# CAN.net
KiCad netlist of a schematic drawn in Altium Designer
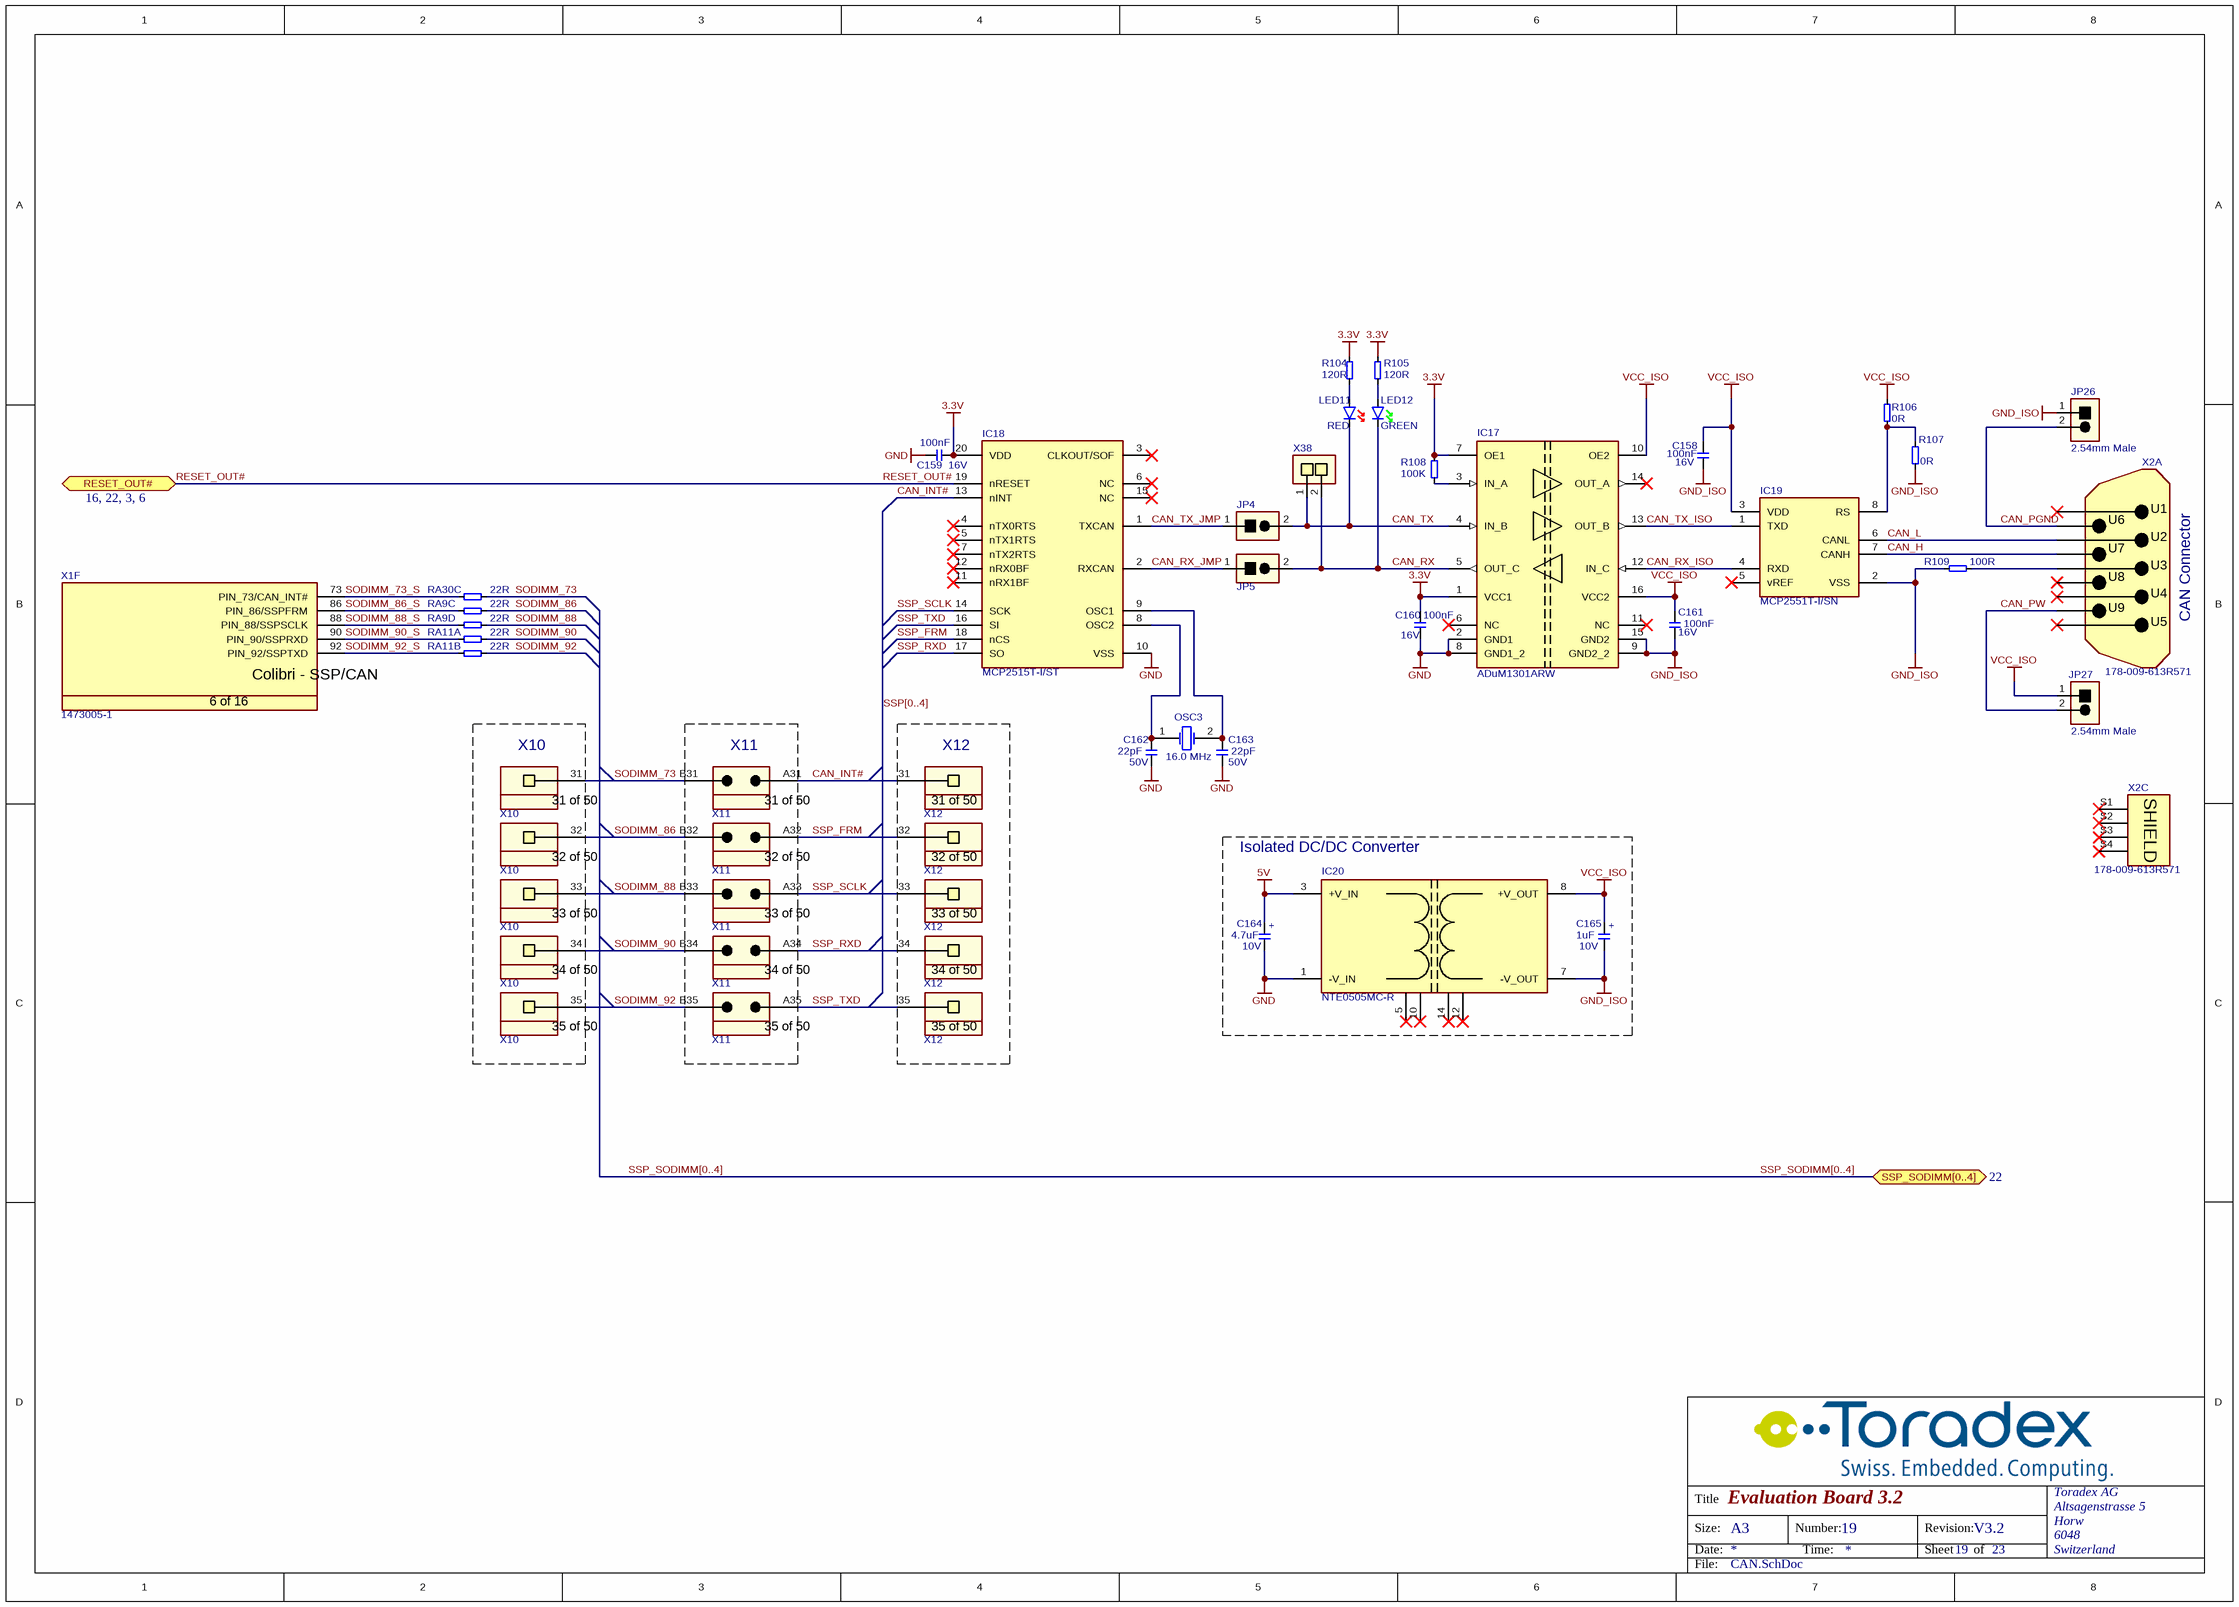
[diagram p0: CAN.SchDoc]

(export (version "E")
  (design (tool "Eeschema 10.0.6"))
  (components
    (comp (ref "C158")
      (value "100nF")
      (footprint "T_CAPC0603X33N")
      (description "Capacitor Ceramic X7R 100nF 16V 10% 0603")
      (fields (field (name "TOLERANCE") "10%") (field (name "RATING") "16V"))
      (libsource (lib "Evaluation Board") (part "C-X7R-100nF-16V-10%-0603"))
    )
    (comp (ref "C159")
      (value "100nF")
      (footprint "T_CAPC0603X33N")
      (description "Capacitor Ceramic X7R 100nF 16V 10% 0603")
      (fields (field (name "TOLERANCE") "10%") (field (name "RATING") "16V"))
      (libsource (lib "Evaluation Board") (part "C-X7R-100nF-16V-10%-0603"))
    )
    (comp (ref "C160")
      (value "100nF")
      (footprint "T_CAPC0603X33N")
      (description "Capacitor Ceramic X7R 100nF 16V 10% 0603")
      (fields (field (name "TOLERANCE") "10%") (field (name "RATING") "16V"))
      (libsource (lib "Evaluation Board") (part "C-X7R-100nF-16V-10%-0603"))
    )
    (comp (ref "C161")
      (value "100nF")
      (footprint "T_CAPC0603X33N")
      (description "Capacitor Ceramic X7R 100nF 16V 10% 0603")
      (fields (field (name "TOLERANCE") "10%") (field (name "RATING") "16V"))
      (libsource (lib "Evaluation Board") (part "C-X7R-100nF-16V-10%-0603"))
    )
    (comp (ref "C162")
      (value "22pF")
      (footprint "T_CAPC0603X33N")
      (description "Capacitor Ceramic NPO 22pF 50V 5% 0603")
      (fields (field (name "TOLERANCE") "5%") (field (name "RATING") "50V"))
      (libsource (lib "Evaluation Board") (part "C-NPO-22pF-50V-5%-0603"))
    )
    (comp (ref "C163")
      (value "22pF")
      (footprint "T_CAPC0603X33N")
      (description "Capacitor Ceramic NPO 22pF 50V 5% 0603")
      (fields (field (name "TOLERANCE") "5%") (field (name "RATING") "50V"))
      (libsource (lib "Evaluation Board") (part "C-NPO-22pF-50V-5%-0603"))
    )
    (comp (ref "C164")
      (value "4.7uF")
      (footprint "T_CAPMP3216X180N")
      (description "Capacitor TA 4.7uF 10V 20% 3216")
      (fields (field (name "TOLERANCE") "20%") (field (name "RATING") "10V"))
      (libsource (lib "Evaluation Board") (part "C-TA-4.7uF-10V-20%-3216"))
    )
    (comp (ref "C165")
      (value "1uF")
      (footprint "T_CAPMP3216X180N")
      (description "Capacitor TA 1uF 10V 20% 3216")
      (fields (field (name "TOLERANCE") "20%") (field (name "RATING") "10V"))
      (libsource (lib "Evaluation Board") (part "C-TA-1uF-10V-20%-3216"))
    )
    (comp (ref "IC17")
      (value "ADuM1301ARW")
      (footprint "T_AD_ADuM1300ARW")
      (description "Digital Isolator")
      (fields (field (name "MANUFACTURER PART NO.") "ADuM1301ARW"))
      (libsource (lib "Evaluation Board") (part "IC-AD-ADuM1301ARW"))
    )
    (comp (ref "IC18")
      (value "MCP2515")
      (footprint "T_MC_MCP2515T-I/ST")
      (description "CAN controller with SPI Interface")
      (fields (field (name "MANUFACTURER PART NO.") "MCP2515T-I/ST"))
      (libsource (lib "Evaluation Board") (part "IC-MC-MCP2515T-I/ST"))
    )
    (comp (ref "IC19")
      (value "MCP2551T-I/SN")
      (footprint "SOIC127P600X173-8N")
      (description "High speed CAN Transceiver")
      (fields (field (name "MANUFACTURER PART NO.") "MCP2551T-I/SN"))
      (libsource (lib "Evaluation Board") (part "IC-MC-MCP2551T-I/SN"))
    )
    (comp (ref "IC20")
      (value "NTE0505MC-R")
      (footprint "T_MURATA_NTE0505MC-R")
      (description "Isolated DC/DC Converter")
      (fields (field (name "MANUFACTURER PART NO.") "NTE0505MC-R"))
      (libsource (lib "Evaluation Board") (part "IC-MUR-NTE0505MC-R"))
    )
    (comp (ref "JP4")
      (value "TSW-101-07-G-D")
      (footprint "T_Samtec_TSW-101-07-G-D")
      (description "Header male, 1x2 Pins, 2.54 mm pitch")
      (libsource (lib "Evaluation Board") (part "CON-Samtec-TSW-101-07-G-D_1"))
    )
    (comp (ref "JP5")
      (value "TSW-101-07-G-D")
      (footprint "T_Samtec_TSW-101-07-G-D")
      (description "Header male, 1x2 Pins, 2.54 mm pitch")
      (libsource (lib "Evaluation Board") (part "CON-Samtec-TSW-101-07-G-D_1"))
    )
    (comp (ref "JP26")
      (value "TSW-101-07-G-D")
      (footprint "T_Samtec_TSW-101-07-G-D")
      (description "Header male, 1x2 Pins, 2.54 mm pitch")
      (libsource (lib "Evaluation Board") (part "CON-Samtec-TSW-101-07-G-D"))
    )
    (comp (ref "JP27")
      (value "TSW-101-07-G-D")
      (footprint "T_Samtec_TSW-101-07-G-D")
      (description "Header male, 1x2 Pins, 2.54 mm pitch")
      (libsource (lib "Evaluation Board") (part "CON-Samtec-TSW-101-07-G-D"))
    )
    (comp (ref "LED11")
      (value "LS T670-K1L2-1")
      (footprint "T_Osram_T670_RED")
      (description "LED red, Osram LS T670-K1L2-1")
      (fields (field (name "COLOR") "RED"))
      (libsource (lib "Evaluation Board") (part "LED-Osram-LS T670-K1L2-1"))
    )
    (comp (ref "LED12")
      (value "LG T670-K1L2-1")
      (footprint "T_Osram_T670_GREEN")
      (description "LED green Osram LG T670-K1L2-1")
      (fields (field (name "COLOR") "GREEN"))
      (libsource (lib "Evaluation Board") (part "LED-Osram-T670-K1L2-1"))
    )
    (comp (ref "OSC3")
      (value "16.0 MHz")
      (footprint "T_RAKON_12SMX")
      (description "Quartz 16.0 MHz")
      (fields
        (field (name "TOLERANCE") "30ppm")
        (field (name "MANUFACTURER PART NO.") "12SMX (B) 30/5020/16")
      )
      (libsource (lib "Evaluation Board") (part "OSC-RAKON-12SMX (B) 30/5020/16-16.0 MHz-30ppm-7.5x5.2mm"))
    )
    (comp (ref "R104")
      (value "120R")
      (footprint "T_RESC0603X30N")
      (description "Resistor 120 ohm 63mW 5% 0603")
      (fields (field (name "TOLERANCE") "5%"))
      (libsource (lib "Evaluation Board") (part "R-120R-63mW-5%-0603"))
    )
    (comp (ref "R105")
      (value "120R")
      (footprint "T_RESC0603X30N")
      (description "Resistor 120 ohm 63mW 5% 0603")
      (fields (field (name "TOLERANCE") "5%"))
      (libsource (lib "Evaluation Board") (part "R-120R-63mW-5%-0603"))
    )
    (comp (ref "R106")
      (value "0R")
      (footprint "T_RESC0603X30N")
      (description "Resistor 0 ohm 63mW 1% 0603")
      (fields (field (name "TOLERANCE") "1%"))
      (libsource (lib "Evaluation Board") (part "R-0R-63mW-1%-0603"))
    )
    (comp (ref "R107")
      (value "0R")
      (footprint "T_RESC0603X30N")
      (description "Resistor 0 ohm 63mW 1% 0603")
      (fields (field (name "TOLERANCE") "1%"))
      (libsource (lib "Evaluation Board") (part "R-0R-63mW-1%-0603"))
    )
    (comp (ref "R108")
      (value "100K")
      (footprint "T_RESC0603X30N")
      (description "Resistor 100 Kohm 63mW 5% 0603")
      (fields (field (name "TOLERANCE") "5%"))
      (libsource (lib "Evaluation Board") (part "R-100KR-63mW-5%-0603"))
    )
    (comp (ref "R109")
      (value "100R")
      (footprint "T_RESC0603X30N")
      (description "Resistor 100 ohm 63mW 5% 0603")
      (fields (field (name "TOLERANCE") "5%"))
      (libsource (lib "Evaluation Board") (part "R-100R-63mW-5%-0603"))
    )
    (comp (ref "RA9")
      (value "22R")
      (footprint "T_Resistor_Array_X4")
      (description "Resistor Array 22 R 63mW 5% 1206")
      (fields (field (name "TOLERANCE") "5%"))
      (libsource (lib "Evaluation Board") (part "RA-22R-63mW-5%-1206-div"))
    )
    (comp (ref "RA11")
      (value "22R")
      (footprint "T_Resistor_Array_X4")
      (description "Resistor Array 22 R 63mW 5% 1206")
      (fields (field (name "TOLERANCE") "5%"))
      (libsource (lib "Evaluation Board") (part "RA-22R-63mW-5%-1206-div"))
    )
    (comp (ref "RA30")
      (value "22R")
      (footprint "T_Resistor_Array_X4")
      (description "Resistor Array 22 R 63mW 5% 1206")
      (fields (field (name "TOLERANCE") "5%"))
      (libsource (lib "Evaluation Board") (part "RA-22R-63mW-5%-1206-div"))
    )
    (comp (ref "X1")
      (value "CON-Tyco-1473005-1-200-0.6mm")
      (footprint "T_Tyco_1473005-1")
      (description "SODIMM Connector")
      (fields (field (name "MANUFACTURER PART NO.") "1473005-1"))
      (libsource (lib "Evaluation Board") (part "CON-Tyco-1473005-1-200-0.6mm"))
    )
    (comp (ref "X2")
      (value "178-009-613R571")
      (footprint "T_NorComp_178-YYY-613R691")
      (description "RS232 Connector 9 pins male")
      (fields (field (name "MANUFACTURER PART NO.") "178-009-613R571"))
      (libsource (lib "Evaluation Board") (part "CON-NorComp-178-009-613R571"))
    )
    (comp (ref "X10")
      (value "SSW-110-01-G-S")
      (footprint "T_Samtec_SSW-110-01-G-S")
      (description "Header 1x50 pin 2.54mm pitch")
      (libsource (lib "") (part "CON-Samtec-SSW-110-01-G-S_1"))
    )
    (comp (ref "X11")
      (value "TSW-110-07-G-D")
      (footprint "T_Samtec_TSW-110-07-G-D")
      (description "Header 2x50 pin 2.54mm pitch")
      (libsource (lib "Evaluation Board") (part "CON-Samtec-TSW-110-07-G-D"))
    )
    (comp (ref "X12")
      (value "SSW-110-01-G-S")
      (footprint "T_Samtec_SSW-110-01-G-S")
      (description "Header 1x50 pin 2.54mm pitch")
      (libsource (lib "Evaluation Board") (part "CON-Samtec-SSW-110-01-G-S"))
    )
    (comp (ref "X38")
      (value "SSW-102-01-G-S")
      (footprint "T_Samtec_SSW-102-01-G-S")
      (description "Receptacle Female, 1x2 Pins, 2.54 mm pitch")
      (libsource (lib "Evaluation Board") (part "CON-Samtec-SSW-102-01-G-S"))
    )
  )
  (nets
    (net (code "11") (name "/CAN_H") (class "Default")
      (node (ref "IC19") (pin "7") (pinfunction "CANH_7") (pintype "passive"))
      (node (ref "X2") (pin "U7") (pinfunction "RTS_U7") (pintype "passive"))
    )
    (net (code "12") (name "/CAN_INT#") (class "Default")
      (node (ref "IC18") (pin "13") (pinfunction "nINT_13") (pintype "passive"))
      (node (ref "X11") (pin "A31") (pinfunction "A31_A31") (pintype "passive"))
      (node (ref "X12") (pin "31") (pinfunction "31_31") (pintype "passive"))
    )
    (net (code "13") (name "/CAN_L") (class "Default")
      (node (ref "IC19") (pin "6") (pinfunction "CANL_6") (pintype "passive"))
      (node (ref "X2") (pin "U2") (pinfunction "RXD_U2") (pintype "passive"))
    )
    (net (code "14") (name "/CAN_PGND") (class "Default")
      (node (ref "JP26") (pin "2") (pinfunction "2_2") (pintype "passive"))
      (node (ref "X2") (pin "U6") (pinfunction "DSR_U6") (pintype "passive"))
    )
    (net (code "15") (name "/CAN_PW") (class "Default")
      (node (ref "JP27") (pin "2") (pinfunction "2_2") (pintype "passive"))
      (node (ref "X2") (pin "U9") (pinfunction "RI_U9") (pintype "passive"))
    )
    (net (code "16") (name "/CAN_RX") (class "Default")
      (node (ref "IC17") (pin "5") (pinfunction "OUT_C_5") (pintype "output"))
      (node (ref "JP5") (pin "2") (pinfunction "2_2") (pintype "passive"))
      (node (ref "LED12") (pin "K") (pinfunction "K_K") (pintype "passive"))
      (node (ref "X38") (pin "2") (pinfunction "2_2") (pintype "passive"))
    )
    (net (code "17") (name "/CAN_RX_ISO") (class "Default")
      (node (ref "IC17") (pin "12") (pinfunction "IN_C_12") (pintype "input"))
      (node (ref "IC19") (pin "4") (pinfunction "RXD_4") (pintype "passive"))
    )
    (net (code "18") (name "/CAN_RX_JMP") (class "Default")
      (node (ref "IC18") (pin "2") (pinfunction "RXCAN_2") (pintype "passive"))
      (node (ref "JP5") (pin "1") (pinfunction "1_1") (pintype "passive"))
    )
    (net (code "19") (name "/CAN_TX") (class "Default")
      (node (ref "IC17") (pin "4") (pinfunction "IN_B_4") (pintype "input"))
      (node (ref "JP4") (pin "2") (pinfunction "2_2") (pintype "passive"))
      (node (ref "LED11") (pin "K") (pinfunction "K_K") (pintype "passive"))
      (node (ref "X38") (pin "1") (pinfunction "1_1") (pintype "passive"))
    )
    (net (code "20") (name "/CAN_TX_ISO") (class "Default")
      (node (ref "IC17") (pin "13") (pinfunction "OUT_B_13") (pintype "output"))
      (node (ref "IC19") (pin "1") (pinfunction "TXD_1") (pintype "passive"))
    )
    (net (code "21") (name "/CAN_TX_JMP") (class "Default")
      (node (ref "IC18") (pin "1") (pinfunction "TXCAN_1") (pintype "passive"))
      (node (ref "JP4") (pin "1") (pinfunction "1_1") (pintype "passive"))
    )
    (net (code "22") (name "/RESET_OUT#") (class "Default")
      (node (ref "IC18") (pin "19") (pinfunction "nRESET_19") (pintype "passive"))
    )
    (net (code "23") (name "/SODIMM_73") (class "Default")
      (node (ref "RA30") (pin "7") (pinfunction "7_7") (pintype "passive"))
      (node (ref "X10") (pin "31") (pinfunction "31_31") (pintype "passive"))
      (node (ref "X11") (pin "B31") (pinfunction "B31_B31") (pintype "passive"))
    )
    (net (code "24") (name "/SODIMM_73_S") (class "Default")
      (node (ref "RA30") (pin "3") (pinfunction "3_3") (pintype "passive"))
      (node (ref "X1") (pin "73") (pinfunction "PIN_73/CAN_INT#_73") (pintype "passive"))
    )
    (net (code "25") (name "/SODIMM_86") (class "Default")
      (node (ref "RA9") (pin "7") (pinfunction "7_7") (pintype "passive"))
      (node (ref "X10") (pin "32") (pinfunction "32_32") (pintype "passive"))
      (node (ref "X11") (pin "B32") (pinfunction "B32_B32") (pintype "passive"))
    )
    (net (code "26") (name "/SODIMM_86_S") (class "Default")
      (node (ref "RA9") (pin "3") (pinfunction "3_3") (pintype "passive"))
      (node (ref "X1") (pin "86") (pinfunction "PIN_86/SSPFRM_86") (pintype "passive"))
    )
    (net (code "27") (name "/SODIMM_88") (class "Default")
      (node (ref "RA9") (pin "8") (pinfunction "8_8") (pintype "passive"))
      (node (ref "X10") (pin "33") (pinfunction "33_33") (pintype "passive"))
      (node (ref "X11") (pin "B33") (pinfunction "B33_B33") (pintype "passive"))
    )
    (net (code "28") (name "/SODIMM_88_S") (class "Default")
      (node (ref "RA9") (pin "4") (pinfunction "4_4") (pintype "passive"))
      (node (ref "X1") (pin "88") (pinfunction "PIN_88/SSPSCLK_88") (pintype "passive"))
    )
    (net (code "29") (name "/SODIMM_90") (class "Default")
      (node (ref "RA11") (pin "5") (pinfunction "5_5") (pintype "passive"))
      (node (ref "X10") (pin "34") (pinfunction "34_34") (pintype "passive"))
      (node (ref "X11") (pin "B34") (pinfunction "B34_B34") (pintype "passive"))
    )
    (net (code "30") (name "/SODIMM_90_S") (class "Default")
      (node (ref "RA11") (pin "1") (pinfunction "1_1") (pintype "passive"))
      (node (ref "X1") (pin "90") (pinfunction "PIN_90/SSPRXD_90") (pintype "passive"))
    )
    (net (code "31") (name "/SODIMM_92") (class "Default")
      (node (ref "RA11") (pin "6") (pinfunction "6_6") (pintype "passive"))
      (node (ref "X10") (pin "35") (pinfunction "35_35") (pintype "passive"))
      (node (ref "X11") (pin "B35") (pinfunction "B35_B35") (pintype "passive"))
    )
    (net (code "32") (name "/SODIMM_92_S") (class "Default")
      (node (ref "RA11") (pin "2") (pinfunction "2_2") (pintype "passive"))
      (node (ref "X1") (pin "92") (pinfunction "PIN_92/SSPTXD_92") (pintype "passive"))
    )
    (net (code "34") (name "/SSP_FRM") (class "Default")
      (node (ref "IC18") (pin "18") (pinfunction "nCS_18") (pintype "passive"))
      (node (ref "X11") (pin "A32") (pinfunction "A32_A32") (pintype "passive"))
      (node (ref "X12") (pin "32") (pinfunction "32_32") (pintype "passive"))
    )
    (net (code "35") (name "/SSP_RXD") (class "Default")
      (node (ref "IC18") (pin "17") (pinfunction "SO_17") (pintype "passive"))
      (node (ref "X11") (pin "A34") (pinfunction "A34_A34") (pintype "passive"))
      (node (ref "X12") (pin "34") (pinfunction "34_34") (pintype "passive"))
    )
    (net (code "36") (name "/SSP_SCLK") (class "Default")
      (node (ref "IC18") (pin "14") (pinfunction "SCK_14") (pintype "passive"))
      (node (ref "X11") (pin "A33") (pinfunction "A33_A33") (pintype "passive"))
      (node (ref "X12") (pin "33") (pinfunction "33_33") (pintype "passive"))
    )
    (net (code "38") (name "/SSP_TXD") (class "Default")
      (node (ref "IC18") (pin "16") (pinfunction "SI_16") (pintype "passive"))
      (node (ref "X11") (pin "A35") (pinfunction "A35_A35") (pintype "passive"))
      (node (ref "X12") (pin "35") (pinfunction "35_35") (pintype "passive"))
    )
    (net (code "39") (name "3.3V") (class "Default")
      (node (ref "C159") (pin "1") (pinfunction "1_1") (pintype "passive"))
      (node (ref "C160") (pin "2") (pinfunction "2_2") (pintype "passive"))
      (node (ref "IC17") (pin "1") (pinfunction "VCC1_1") (pintype "passive"))
      (node (ref "IC17") (pin "7") (pinfunction "OE1_7") (pintype "passive"))
      (node (ref "IC18") (pin "20") (pinfunction "VDD_20") (pintype "passive"))
      (node (ref "R104") (pin "1") (pinfunction "1_1") (pintype "passive"))
      (node (ref "R105") (pin "1") (pinfunction "1_1") (pintype "passive"))
      (node (ref "R108") (pin "2") (pinfunction "2_2") (pintype "passive"))
    )
    (net (code "40") (name "5V") (class "Default")
      (node (ref "C164") (pin "1") (pinfunction "1_1") (pintype "passive"))
      (node (ref "IC20") (pin "3") (pinfunction "+V_IN_3") (pintype "power_in"))
    )
    (net (code "41") (name "GND") (class "Default")
      (node (ref "C159") (pin "2") (pinfunction "2_2") (pintype "passive"))
      (node (ref "C160") (pin "1") (pinfunction "1_1") (pintype "passive"))
      (node (ref "C162") (pin "1") (pinfunction "1_1") (pintype "passive"))
      (node (ref "C163") (pin "1") (pinfunction "1_1") (pintype "passive"))
      (node (ref "C164") (pin "2") (pinfunction "2_2") (pintype "passive"))
      (node (ref "IC17") (pin "2") (pinfunction "GND1_2") (pintype "power_in"))
      (node (ref "IC17") (pin "8") (pinfunction "GND1_2_8") (pintype "power_in"))
      (node (ref "IC18") (pin "10") (pinfunction "VSS_10") (pintype "power_in"))
      (node (ref "IC20") (pin "1") (pinfunction "-V_IN_1") (pintype "power_in"))
    )
    (net (code "42") (name "GND_ISO") (class "Default")
      (node (ref "C158") (pin "1") (pinfunction "1_1") (pintype "passive"))
      (node (ref "C161") (pin "1") (pinfunction "1_1") (pintype "passive"))
      (node (ref "C165") (pin "2") (pinfunction "2_2") (pintype "passive"))
      (node (ref "IC17") (pin "15") (pinfunction "GND2_15") (pintype "power_in"))
      (node (ref "IC17") (pin "9") (pinfunction "GND2_2_9") (pintype "power_in"))
      (node (ref "IC19") (pin "2") (pinfunction "VSS_2") (pintype "passive"))
      (node (ref "IC20") (pin "7") (pinfunction "-V_OUT_7") (pintype "power_in"))
      (node (ref "JP26") (pin "1") (pinfunction "1_1") (pintype "passive"))
      (node (ref "R107") (pin "1") (pinfunction "1_1") (pintype "passive"))
      (node (ref "R109") (pin "2") (pinfunction "2_2") (pintype "passive"))
    )
    (net (code "43") (name "Net-(IC17-IN_A)") (class "Default")
      (node (ref "IC17") (pin "3") (pinfunction "IN_A_3") (pintype "input"))
      (node (ref "R108") (pin "1") (pinfunction "1_1") (pintype "passive"))
    )
    (net (code "44") (name "Net-(IC18-OSC1)") (class "Default")
      (node (ref "C163") (pin "2") (pinfunction "2_2") (pintype "passive"))
      (node (ref "IC18") (pin "9") (pinfunction "OSC1_9") (pintype "passive"))
      (node (ref "OSC3") (pin "2") (pinfunction "OSC2_2") (pintype "passive"))
    )
    (net (code "45") (name "Net-(IC18-OSC2)") (class "Default")
      (node (ref "C162") (pin "2") (pinfunction "2_2") (pintype "passive"))
      (node (ref "IC18") (pin "8") (pinfunction "OSC2_8") (pintype "passive"))
      (node (ref "OSC3") (pin "1") (pinfunction "OSC1_1") (pintype "passive"))
    )
    (net (code "46") (name "Net-(IC19-RS)") (class "Default")
      (node (ref "IC19") (pin "8") (pinfunction "RS_8") (pintype "passive"))
      (node (ref "R106") (pin "1") (pinfunction "1_1") (pintype "passive"))
      (node (ref "R107") (pin "2") (pinfunction "2_2") (pintype "passive"))
    )
    (net (code "47") (name "Net-(LED11-PadA)") (class "Default")
      (node (ref "LED11") (pin "A") (pinfunction "A_A") (pintype "passive"))
      (node (ref "R104") (pin "2") (pinfunction "2_2") (pintype "passive"))
    )
    (net (code "48") (name "Net-(LED12-PadA)") (class "Default")
      (node (ref "LED12") (pin "A") (pinfunction "A_A") (pintype "passive"))
      (node (ref "R105") (pin "2") (pinfunction "2_2") (pintype "passive"))
    )
    (net (code "49") (name "Net-(X2A-TXD)") (class "Default")
      (node (ref "R109") (pin "1") (pinfunction "1_1") (pintype "passive"))
      (node (ref "X2") (pin "U3") (pinfunction "TXD_U3") (pintype "passive"))
    )
    (net (code "50") (name "VCC_ISO") (class "Default")
      (node (ref "C158") (pin "2") (pinfunction "2_2") (pintype "passive"))
      (node (ref "C161") (pin "2") (pinfunction "2_2") (pintype "passive"))
      (node (ref "C165") (pin "1") (pinfunction "1_1") (pintype "passive"))
      (node (ref "IC17") (pin "10") (pinfunction "OE2_10") (pintype "passive"))
      (node (ref "IC17") (pin "16") (pinfunction "VCC2_16") (pintype "passive"))
      (node (ref "IC19") (pin "3") (pinfunction "VDD_3") (pintype "passive"))
      (node (ref "IC20") (pin "8") (pinfunction "+V_OUT_8") (pintype "power_in"))
      (node (ref "JP27") (pin "1") (pinfunction "1_1") (pintype "passive"))
      (node (ref "R106") (pin "2") (pinfunction "2_2") (pintype "passive"))
    )
    (net (code "51") (name "unconnected-(IC17-NC-Pad6)") (class "Default")
      (node (ref "IC17") (pin "6") (pinfunction "NC_6") (pintype "passive+no_connect"))
    )
    (net (code "52") (name "unconnected-(IC17-NC-Pad11)") (class "Default")
      (node (ref "IC17") (pin "11") (pinfunction "NC_11") (pintype "passive+no_connect"))
    )
    (net (code "53") (name "unconnected-(IC17-OUT_A-Pad14)") (class "Default")
      (node (ref "IC17") (pin "14") (pinfunction "OUT_A_14") (pintype "output+no_connect"))
    )
    (net (code "54") (name "unconnected-(IC18-CLKOUT{slash}SOF-Pad3)") (class "Default")
      (node (ref "IC18") (pin "3") (pinfunction "CLKOUT/SOF_3") (pintype "passive+no_connect"))
    )
    (net (code "55") (name "unconnected-(IC18-NC-Pad6)") (class "Default")
      (node (ref "IC18") (pin "6") (pinfunction "NC_6") (pintype "passive+no_connect"))
    )
    (net (code "56") (name "unconnected-(IC18-NC-Pad15)") (class "Default")
      (node (ref "IC18") (pin "15") (pinfunction "NC_15") (pintype "passive+no_connect"))
    )
    (net (code "57") (name "unconnected-(IC18-nRX0BF-Pad12)") (class "Default")
      (node (ref "IC18") (pin "12") (pinfunction "nRX0BF_12") (pintype "passive+no_connect"))
    )
    (net (code "58") (name "unconnected-(IC18-nRX1BF-Pad11)") (class "Default")
      (node (ref "IC18") (pin "11") (pinfunction "nRX1BF_11") (pintype "passive+no_connect"))
    )
    (net (code "59") (name "unconnected-(IC18-nTX0RTS-Pad4)") (class "Default")
      (node (ref "IC18") (pin "4") (pinfunction "nTX0RTS_4") (pintype "passive+no_connect"))
    )
    (net (code "60") (name "unconnected-(IC18-nTX1RTS-Pad5)") (class "Default")
      (node (ref "IC18") (pin "5") (pinfunction "nTX1RTS_5") (pintype "passive+no_connect"))
    )
    (net (code "61") (name "unconnected-(IC18-nTX2RTS-Pad7)") (class "Default")
      (node (ref "IC18") (pin "7") (pinfunction "nTX2RTS_7") (pintype "passive+no_connect"))
    )
    (net (code "62") (name "unconnected-(IC19-vREF-Pad5)") (class "Default")
      (node (ref "IC19") (pin "5") (pinfunction "vREF_5") (pintype "passive+no_connect"))
    )
    (net (code "63") (name "unconnected-(IC20-NC-Pad5)") (class "Default")
      (node (ref "IC20") (pin "5") (pinfunction "NC_5") (pintype "passive+no_connect"))
    )
    (net (code "64") (name "unconnected-(IC20-NC-Pad10)") (class "Default")
      (node (ref "IC20") (pin "10") (pinfunction "NC_10") (pintype "passive+no_connect"))
    )
    (net (code "65") (name "unconnected-(IC20-NC-Pad12)") (class "Default")
      (node (ref "IC20") (pin "12") (pinfunction "NC_12") (pintype "passive+no_connect"))
    )
    (net (code "66") (name "unconnected-(IC20-NC-Pad14)") (class "Default")
      (node (ref "IC20") (pin "14") (pinfunction "NC_14") (pintype "passive+no_connect"))
    )
    (net (code "67") (name "unconnected-(X2A-CTS-PadU8)") (class "Default")
      (node (ref "X2") (pin "U8") (pinfunction "CTS_U8") (pintype "passive+no_connect"))
    )
    (net (code "68") (name "unconnected-(X2A-DCD-PadU1)") (class "Default")
      (node (ref "X2") (pin "U1") (pinfunction "DCD_U1") (pintype "passive+no_connect"))
    )
    (net (code "69") (name "unconnected-(X2A-DTR-PadU4)") (class "Default")
      (node (ref "X2") (pin "U4") (pinfunction "DTR_U4") (pintype "passive+no_connect"))
    )
    (net (code "70") (name "unconnected-(X2A-GND-PadU5)") (class "Default")
      (node (ref "X2") (pin "U5") (pinfunction "GND_U5") (pintype "passive+no_connect"))
    )
    (net (code "71") (name "unconnected-(X2C-SHIELD-PadS1)") (class "Default")
      (node (ref "X2") (pin "S1") (pinfunction "SHIELD_S1") (pintype "passive+no_connect"))
    )
    (net (code "72") (name "unconnected-(X2C-SHIELD-PadS2)") (class "Default")
      (node (ref "X2") (pin "S2") (pinfunction "SHIELD_S2") (pintype "passive+no_connect"))
    )
    (net (code "73") (name "unconnected-(X2C-SHIELD-PadS3)") (class "Default")
      (node (ref "X2") (pin "S3") (pinfunction "SHIELD_S3") (pintype "passive+no_connect"))
    )
    (net (code "74") (name "unconnected-(X2C-SHIELD-PadS4)") (class "Default")
      (node (ref "X2") (pin "S4") (pinfunction "SHIELD_S4") (pintype "passive+no_connect"))
    )
  )
)
